# CONNECTIONS.net
KiCad netlist of a schematic drawn in Altium Designer
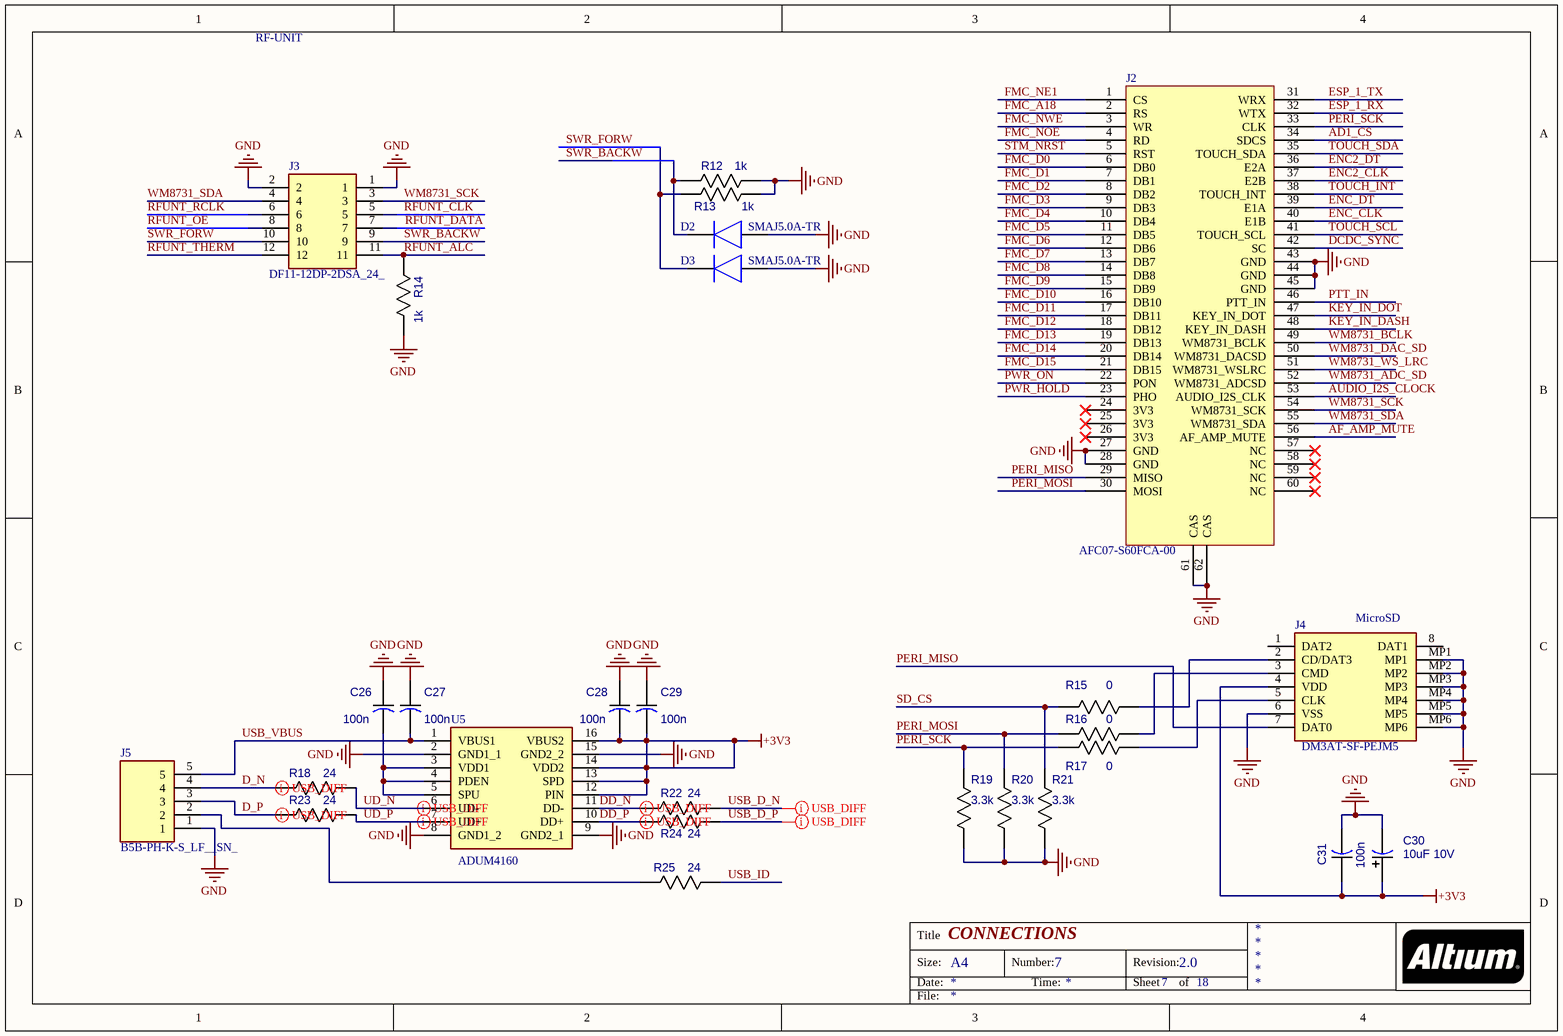
[diagram p0: CONNECTIONS.SchDoc]

(export (version "E")
  (design (tool "Eeschema 10.0.6"))
  (components
    (comp (ref "C26")
      (value "100n")
      (footprint "CAP_0805")
      (description "CAP_0805")
      (libsource (lib "*") (part "CAP_0805"))
    )
    (comp (ref "C27")
      (value "100n")
      (footprint "CAP_0805")
      (description "CAP_0805")
      (libsource (lib "*") (part "CAP_0805"))
    )
    (comp (ref "C28")
      (value "100n")
      (footprint "CAP_0805")
      (description "CAP_0805")
      (libsource (lib "*") (part "CAP_0805"))
    )
    (comp (ref "C29")
      (value "100n")
      (footprint "CAP_0805")
      (description "CAP_0805")
      (libsource (lib "*") (part "CAP_0805"))
    )
    (comp (ref "C30")
      (value "10uF 10V")
      (footprint "CAPAE_4.3x4.3h5.4")
      (description "CAPAE_4.3x4.3h5.4")
      (fields (field (name "Comment") "22uF 10V"))
      (libsource (lib "*") (part "CAPAE_4.3x4.3h5.4"))
    )
    (comp (ref "C31")
      (value "100n")
      (footprint "CAP_0805")
      (description "CAP_0805")
      (libsource (lib "") (part "CAP_0805_1"))
    )
    (comp (ref "D2")
      (value "SMAJ5.0A-TR")
      (footprint "SMBJ36CATR")
      (description "Diode")
      (fields
        (field (name "MANUFACTURER_PART_NUMBER") "SMLVT3V3")
        (field (name "MOUSER PART NUMBER") "511-SMLVT3V3")
      )
      (libsource (lib "*") (part "SMLVT3V3"))
    )
    (comp (ref "D3")
      (value "SMAJ5.0A-TR")
      (footprint "SMBJ36CATR")
      (description "Diode")
      (fields
        (field (name "MANUFACTURER_PART_NUMBER") "SMLVT3V3")
        (field (name "MOUSER PART NUMBER") "511-SMLVT3V3")
      )
      (libsource (lib "*") (part "SMLVT3V3"))
    )
    (comp (ref "J2")
      (value "AFC07-S60FCA-00")
      (footprint "AFC07-S60FCA-00")
      (libsource (lib "MOTHERBOARD") (part "AFC07-S60FCA-00"))
    )
    (comp (ref "J3")
      (value "DF11-12DP-2DSA_24_")
      (footprint "SamacSys:SHDR12W60P200_2X6_1400X500X690P")
      (description "Connector")
      (fields
        (field (name "MANUFACTURER_PART_NUMBER") "DF11-12DP-2DSA(24)")
        (field (name "MOUSER PART NUMBER") "798-DF11-12DP-2DSA24")
      )
      (libsource (lib "*") (part "DF11-12DP-2DSA_24_"))
    )
    (comp (ref "J4")
      (value "DM3AT-SF-PEJM5")
      (footprint "SamacSys:DM3ATSFPEJM5")
      (description "Connector")
      (libsource (lib "*") (part "DM3AT-SF-PEJM5"))
    )
    (comp (ref "J5")
      (value "B5B-PH-K-S_LF__SN_")
      (footprint "SamacSys:SHDR5W50P0X200_1X5_1190X450X600P")
      (description "Connector")
      (fields (field (name "MANUFACTURER_PART_NUMBER") "B5B-PH-K-S(LF)(SN)"))
      (libsource (lib "SamacSys") (part "B5B-PH-K-S_LF__SN_"))
    )
    (comp (ref "R12")
      (value "1k")
      (footprint "RES_0805")
      (description "RES_0805")
      (libsource (lib "") (part "RES_0805_1"))
    )
    (comp (ref "R13")
      (value "1k")
      (footprint "RES_0805")
      (description "RES_0805")
      (libsource (lib "") (part "RES_0805_1"))
    )
    (comp (ref "R14")
      (value "1k")
      (footprint "RES_0805")
      (description "RES_0805")
      (libsource (lib "") (part "RES_0805_1"))
    )
    (comp (ref "R15")
      (value "0")
      (footprint "RES_0805")
      (description "RES_0805")
      (libsource (lib "*") (part "RES_0805"))
    )
    (comp (ref "R16")
      (value "0")
      (footprint "RES_0805")
      (description "RES_0805")
      (libsource (lib "*") (part "RES_0805"))
    )
    (comp (ref "R17")
      (value "0")
      (footprint "RES_0805")
      (description "RES_0805")
      (libsource (lib "*") (part "RES_0805"))
    )
    (comp (ref "R18")
      (value "24")
      (footprint "RES_0805")
      (description "RES_0805")
      (libsource (lib "") (part "RES_0805_1"))
    )
    (comp (ref "R19")
      (value "3.3k")
      (footprint "RES_0805")
      (description "RES_0805")
      (libsource (lib "*") (part "RES_0805"))
    )
    (comp (ref "R20")
      (value "3.3k")
      (footprint "RES_0805")
      (description "RES_0805")
      (libsource (lib "*") (part "RES_0805"))
    )
    (comp (ref "R21")
      (value "3.3k")
      (footprint "RES_0805")
      (description "RES_0805")
      (libsource (lib "*") (part "RES_0805"))
    )
    (comp (ref "R22")
      (value "24")
      (footprint "RES_0805")
      (description "RES_0805")
      (libsource (lib "") (part "RES_0805_1"))
    )
    (comp (ref "R23")
      (value "24")
      (footprint "RES_0805")
      (description "RES_0805")
      (libsource (lib "") (part "RES_0805_1"))
    )
    (comp (ref "R24")
      (value "24")
      (footprint "RES_0805")
      (description "RES_0805")
      (libsource (lib "") (part "RES_0805_1"))
    )
    (comp (ref "R25")
      (value "24")
      (footprint "RES_0805")
      (description "RES_0805")
      (libsource (lib "") (part "RES_0805_1"))
    )
    (comp (ref "U5")
      (value "ADUM4160")
      (footprint "SOIC127P1032X265-16N")
      (description "Integrated Circuit")
      (fields
        (field (name "MANUFACTURER_PART_NUMBER") "ADUM4160BRWZ")
        (field (name "MOUSER PART NUMBER") "584-ADUM4160BRWZ")
      )
      (libsource (lib "*") (part "ADUM4160BRWZ"))
    )
  )
  (nets
    (net (code "1") (name "+3V3") (class "Default")
      (node (ref "C28") (pin "2") (pinfunction "2_2") (pintype "passive"))
      (node (ref "C29") (pin "2") (pinfunction "2_2") (pintype "passive"))
      (node (ref "C30") (pin "1") (pinfunction "PLUS_1") (pintype "passive"))
      (node (ref "C31") (pin "1") (pinfunction "1_1") (pintype "passive"))
      (node (ref "J4") (pin "4") (pinfunction "VDD_4") (pintype "passive"))
      (node (ref "U5") (pin "12") (pinfunction "PIN_12") (pintype "passive"))
      (node (ref "U5") (pin "13") (pinfunction "SPD_13") (pintype "passive"))
      (node (ref "U5") (pin "14") (pinfunction "VDD2_14") (pintype "passive"))
      (node (ref "U5") (pin "16") (pinfunction "VBUS2_16") (pintype "passive"))
    )
    (net (code "2") (name "/AD1_CS") (class "Default")
      (node (ref "J2") (pin "34") (pinfunction "SDCS_34") (pintype "passive"))
    )
    (net (code "3") (name "/AF_AMP_MUTE") (class "Default")
      (node (ref "J2") (pin "56") (pinfunction "AF_AMP_MUTE_56") (pintype "passive"))
    )
    (net (code "4") (name "/AUDIO_I2S_CLOCK") (class "Default")
      (node (ref "J2") (pin "53") (pinfunction "AUDIO_I2S_CLK_53") (pintype "passive"))
    )
    (net (code "5") (name "/DCDC_SYNC") (class "Default")
      (node (ref "J2") (pin "42") (pinfunction "SC_42") (pintype "passive"))
    )
    (net (code "6") (name "/DD_N") (class "Default")
      (node (ref "R22") (pin "1") (pinfunction "1_1") (pintype "passive"))
      (node (ref "U5") (pin "11") (pinfunction "DD-_11") (pintype "passive"))
    )
    (net (code "7") (name "/DD_P") (class "Default")
      (node (ref "R24") (pin "1") (pinfunction "1_1") (pintype "passive"))
      (node (ref "U5") (pin "10") (pinfunction "DD+_10") (pintype "passive"))
    )
    (net (code "8") (name "/D_N") (class "Default")
      (node (ref "J5") (pin "4") (pinfunction "4_4") (pintype "passive"))
      (node (ref "R18") (pin "1") (pinfunction "1_1") (pintype "passive"))
    )
    (net (code "9") (name "/D_P") (class "Default")
      (node (ref "J5") (pin "3") (pinfunction "3_3") (pintype "passive"))
      (node (ref "R23") (pin "1") (pinfunction "1_1") (pintype "passive"))
    )
    (net (code "10") (name "/ENC2_CLK") (class "Default")
      (node (ref "J2") (pin "37") (pinfunction "E2B_37") (pintype "passive"))
    )
    (net (code "11") (name "/ENC2_DT") (class "Default")
      (node (ref "J2") (pin "36") (pinfunction "E2A_36") (pintype "passive"))
    )
    (net (code "12") (name "/ENC_CLK") (class "Default")
      (node (ref "J2") (pin "40") (pinfunction "E1B_40") (pintype "passive"))
    )
    (net (code "13") (name "/ENC_DT") (class "Default")
      (node (ref "J2") (pin "39") (pinfunction "E1A_39") (pintype "passive"))
    )
    (net (code "14") (name "/ESP_1_RX") (class "Default")
      (node (ref "J2") (pin "32") (pinfunction "WTX_32") (pintype "passive"))
    )
    (net (code "15") (name "/ESP_1_TX") (class "Default")
      (node (ref "J2") (pin "31") (pinfunction "WRX_31") (pintype "passive"))
    )
    (net (code "16") (name "/FMC_A18") (class "Default")
      (node (ref "J2") (pin "2") (pinfunction "RS_2") (pintype "passive"))
    )
    (net (code "17") (name "/FMC_D0") (class "Default")
      (node (ref "J2") (pin "6") (pinfunction "DB0_6") (pintype "passive"))
    )
    (net (code "18") (name "/FMC_D1") (class "Default")
      (node (ref "J2") (pin "7") (pinfunction "DB1_7") (pintype "passive"))
    )
    (net (code "19") (name "/FMC_D2") (class "Default")
      (node (ref "J2") (pin "8") (pinfunction "DB2_8") (pintype "passive"))
    )
    (net (code "20") (name "/FMC_D3") (class "Default")
      (node (ref "J2") (pin "9") (pinfunction "DB3_9") (pintype "passive"))
    )
    (net (code "21") (name "/FMC_D4") (class "Default")
      (node (ref "J2") (pin "10") (pinfunction "DB4_10") (pintype "passive"))
    )
    (net (code "22") (name "/FMC_D5") (class "Default")
      (node (ref "J2") (pin "11") (pinfunction "DB5_11") (pintype "passive"))
    )
    (net (code "23") (name "/FMC_D6") (class "Default")
      (node (ref "J2") (pin "12") (pinfunction "DB6_12") (pintype "passive"))
    )
    (net (code "24") (name "/FMC_D7") (class "Default")
      (node (ref "J2") (pin "13") (pinfunction "DB7_13") (pintype "passive"))
    )
    (net (code "25") (name "/FMC_D8") (class "Default")
      (node (ref "J2") (pin "14") (pinfunction "DB8_14") (pintype "passive"))
    )
    (net (code "26") (name "/FMC_D9") (class "Default")
      (node (ref "J2") (pin "15") (pinfunction "DB9_15") (pintype "passive"))
    )
    (net (code "27") (name "/FMC_D10") (class "Default")
      (node (ref "J2") (pin "16") (pinfunction "DB10_16") (pintype "passive"))
    )
    (net (code "28") (name "/FMC_D11") (class "Default")
      (node (ref "J2") (pin "17") (pinfunction "DB11_17") (pintype "passive"))
    )
    (net (code "29") (name "/FMC_D12") (class "Default")
      (node (ref "J2") (pin "18") (pinfunction "DB12_18") (pintype "passive"))
    )
    (net (code "30") (name "/FMC_D13") (class "Default")
      (node (ref "J2") (pin "19") (pinfunction "DB13_19") (pintype "passive"))
    )
    (net (code "31") (name "/FMC_D14") (class "Default")
      (node (ref "J2") (pin "20") (pinfunction "DB14_20") (pintype "passive"))
    )
    (net (code "32") (name "/FMC_D15") (class "Default")
      (node (ref "J2") (pin "21") (pinfunction "DB15_21") (pintype "passive"))
    )
    (net (code "33") (name "/FMC_NE1") (class "Default")
      (node (ref "J2") (pin "1") (pinfunction "CS_1") (pintype "passive"))
    )
    (net (code "34") (name "/FMC_NOE") (class "Default")
      (node (ref "J2") (pin "4") (pinfunction "RD_4") (pintype "passive"))
    )
    (net (code "35") (name "/FMC_NWE") (class "Default")
      (node (ref "J2") (pin "3") (pinfunction "WR_3") (pintype "passive"))
    )
    (net (code "36") (name "/KEY_IN_DASH") (class "Default")
      (node (ref "J2") (pin "48") (pinfunction "KEY_IN_DASH_48") (pintype "passive"))
    )
    (net (code "37") (name "/KEY_IN_DOT") (class "Default")
      (node (ref "J2") (pin "47") (pinfunction "KEY_IN_DOT_47") (pintype "passive"))
    )
    (net (code "38") (name "/PERI_MISO") (class "Default")
      (node (ref "J2") (pin "29") (pinfunction "MISO_29") (pintype "passive"))
      (node (ref "J4") (pin "7") (pinfunction "DAT0_7") (pintype "passive"))
    )
    (net (code "39") (name "/PERI_MOSI") (class "Default")
      (node (ref "J2") (pin "30") (pinfunction "MOSI_30") (pintype "passive"))
      (node (ref "R16") (pin "2") (pinfunction "2_2") (pintype "passive"))
      (node (ref "R20") (pin "2") (pinfunction "2_2") (pintype "passive"))
    )
    (net (code "40") (name "/PERI_SCK") (class "Default")
      (node (ref "J2") (pin "33") (pinfunction "CLK_33") (pintype "passive"))
      (node (ref "R17") (pin "2") (pinfunction "2_2") (pintype "passive"))
      (node (ref "R19") (pin "2") (pinfunction "2_2") (pintype "passive"))
    )
    (net (code "41") (name "/PTT_IN") (class "Default")
      (node (ref "J2") (pin "46") (pinfunction "PTT_IN_46") (pintype "passive"))
    )
    (net (code "42") (name "/PWR_HOLD") (class "Default")
      (node (ref "J2") (pin "23") (pinfunction "PHO_23") (pintype "passive"))
    )
    (net (code "43") (name "/PWR_ON") (class "Default")
      (node (ref "J2") (pin "22") (pinfunction "PON_22") (pintype "passive"))
    )
    (net (code "44") (name "/RFUNT_ALC") (class "Default")
      (node (ref "J3") (pin "11") (pinfunction "11_11") (pintype "passive"))
      (node (ref "R14") (pin "1") (pinfunction "1_1") (pintype "passive"))
    )
    (net (code "45") (name "/RFUNT_CLK") (class "Default")
      (node (ref "J3") (pin "5") (pinfunction "5_5") (pintype "passive"))
    )
    (net (code "46") (name "/RFUNT_DATA") (class "Default")
      (node (ref "J3") (pin "7") (pinfunction "7_7") (pintype "passive"))
    )
    (net (code "47") (name "/RFUNT_OE") (class "Default")
      (node (ref "J3") (pin "8") (pinfunction "8_8") (pintype "passive"))
    )
    (net (code "48") (name "/RFUNT_RCLK") (class "Default")
      (node (ref "J3") (pin "6") (pinfunction "6_6") (pintype "passive"))
    )
    (net (code "49") (name "/RFUNT_THERM") (class "Default")
      (node (ref "J3") (pin "12") (pinfunction "12_12") (pintype "passive"))
    )
    (net (code "50") (name "/SD_CS") (class "Default")
      (node (ref "R15") (pin "2") (pinfunction "2_2") (pintype "passive"))
      (node (ref "R21") (pin "2") (pinfunction "2_2") (pintype "passive"))
    )
    (net (code "51") (name "/STM_NRST") (class "Default")
      (node (ref "J2") (pin "5") (pinfunction "RST_5") (pintype "passive"))
    )
    (net (code "52") (name "/SWR_BACKW") (class "Default")
      (node (ref "D2") (pin "1") (pinfunction "K_1") (pintype "passive"))
      (node (ref "J3") (pin "9") (pinfunction "9_9") (pintype "passive"))
      (node (ref "R12") (pin "1") (pinfunction "1_1") (pintype "passive"))
    )
    (net (code "53") (name "/SWR_FORW") (class "Default")
      (node (ref "D3") (pin "1") (pinfunction "K_1") (pintype "passive"))
      (node (ref "J3") (pin "10") (pinfunction "10_10") (pintype "passive"))
      (node (ref "R13") (pin "1") (pinfunction "1_1") (pintype "passive"))
    )
    (net (code "54") (name "/TOUCH_INT") (class "Default")
      (node (ref "J2") (pin "38") (pinfunction "TOUCH_INT_38") (pintype "passive"))
    )
    (net (code "55") (name "/TOUCH_SCL") (class "Default")
      (node (ref "J2") (pin "41") (pinfunction "TOUCH_SCL_41") (pintype "passive"))
    )
    (net (code "56") (name "/TOUCH_SDA") (class "Default")
      (node (ref "J2") (pin "35") (pinfunction "TOUCH_SDA_35") (pintype "passive"))
    )
    (net (code "57") (name "/UD_N") (class "Default")
      (node (ref "R18") (pin "2") (pinfunction "2_2") (pintype "passive"))
      (node (ref "U5") (pin "6") (pinfunction "UD-_6") (pintype "passive"))
    )
    (net (code "58") (name "/UD_P") (class "Default")
      (node (ref "R23") (pin "2") (pinfunction "2_2") (pintype "passive"))
      (node (ref "U5") (pin "7") (pinfunction "UD+_7") (pintype "passive"))
    )
    (net (code "59") (name "/USB_D_N") (class "Default")
      (node (ref "R22") (pin "2") (pinfunction "2_2") (pintype "passive"))
    )
    (net (code "60") (name "/USB_D_P") (class "Default")
      (node (ref "R24") (pin "2") (pinfunction "2_2") (pintype "passive"))
    )
    (net (code "61") (name "/USB_ID") (class "Default")
      (node (ref "R25") (pin "2") (pinfunction "2_2") (pintype "passive"))
    )
    (net (code "62") (name "/USB_VBUS") (class "Default")
      (node (ref "C27") (pin "2") (pinfunction "2_2") (pintype "passive"))
      (node (ref "J5") (pin "5") (pinfunction "5_5") (pintype "passive"))
      (node (ref "U5") (pin "1") (pinfunction "VBUS1_1") (pintype "passive"))
    )
    (net (code "63") (name "/WM8731_ADC_SD") (class "Default")
      (node (ref "J2") (pin "52") (pinfunction "WM8731_ADCSD_52") (pintype "passive"))
    )
    (net (code "64") (name "/WM8731_BCLK") (class "Default")
      (node (ref "J2") (pin "49") (pinfunction "WM8731_BCLK_49") (pintype "passive"))
    )
    (net (code "65") (name "/WM8731_DAC_SD") (class "Default")
      (node (ref "J2") (pin "50") (pinfunction "WM8731_DACSD_50") (pintype "passive"))
    )
    (net (code "66") (name "/WM8731_SCK") (class "Default")
      (node (ref "J2") (pin "54") (pinfunction "WM8731_SCK_54") (pintype "passive"))
      (node (ref "J3") (pin "3") (pinfunction "3_3") (pintype "passive"))
    )
    (net (code "67") (name "/WM8731_SDA") (class "Default")
      (node (ref "J2") (pin "55") (pinfunction "WM8731_SDA_55") (pintype "passive"))
      (node (ref "J3") (pin "4") (pinfunction "4_4") (pintype "passive"))
    )
    (net (code "68") (name "/WM8731_WS_LRC") (class "Default")
      (node (ref "J2") (pin "51") (pinfunction "WM8731_WSLRC_51") (pintype "passive"))
    )
    (net (code "69") (name "GND") (class "Default")
      (node (ref "C26") (pin "1") (pinfunction "1_1") (pintype "passive"))
      (node (ref "C27") (pin "1") (pinfunction "1_1") (pintype "passive"))
      (node (ref "C28") (pin "1") (pinfunction "1_1") (pintype "passive"))
      (node (ref "C29") (pin "1") (pinfunction "1_1") (pintype "passive"))
      (node (ref "C30") (pin "2") (pinfunction "MINUS_2") (pintype "passive"))
      (node (ref "C31") (pin "2") (pinfunction "2_2") (pintype "passive"))
      (node (ref "D2") (pin "2") (pinfunction "A_2") (pintype "passive"))
      (node (ref "D3") (pin "2") (pinfunction "A_2") (pintype "passive"))
      (node (ref "J2") (pin "27") (pinfunction "GND_27") (pintype "passive"))
      (node (ref "J2") (pin "28") (pinfunction "GND_28") (pintype "passive"))
      (node (ref "J2") (pin "43") (pinfunction "GND_43") (pintype "passive"))
      (node (ref "J2") (pin "44") (pinfunction "GND_44") (pintype "passive"))
      (node (ref "J2") (pin "45") (pinfunction "GND_45") (pintype "passive"))
      (node (ref "J2") (pin "61") (pinfunction "CAS_61") (pintype "passive"))
      (node (ref "J2") (pin "62") (pinfunction "CAS_62") (pintype "passive"))
      (node (ref "J3") (pin "1") (pinfunction "1_1") (pintype "passive"))
      (node (ref "J3") (pin "2") (pinfunction "2_2") (pintype "passive"))
      (node (ref "J4") (pin "6") (pinfunction "VSS_6") (pintype "passive"))
      (node (ref "J4") (pin "MP1") (pinfunction "MP1_MP1") (pintype "passive"))
      (node (ref "J4") (pin "MP2") (pinfunction "MP2_MP2") (pintype "passive"))
      (node (ref "J4") (pin "MP3") (pinfunction "MP3_MP3") (pintype "passive"))
      (node (ref "J4") (pin "MP4") (pinfunction "MP4_MP4") (pintype "passive"))
      (node (ref "J4") (pin "MP5") (pinfunction "MP5_MP5") (pintype "passive"))
      (node (ref "J4") (pin "MP6") (pinfunction "MP6_MP6") (pintype "passive"))
      (node (ref "J5") (pin "1") (pinfunction "1_1") (pintype "passive"))
      (node (ref "R12") (pin "2") (pinfunction "2_2") (pintype "passive"))
      (node (ref "R13") (pin "2") (pinfunction "2_2") (pintype "passive"))
      (node (ref "R14") (pin "2") (pinfunction "2_2") (pintype "passive"))
      (node (ref "R19") (pin "1") (pinfunction "1_1") (pintype "passive"))
      (node (ref "R20") (pin "1") (pinfunction "1_1") (pintype "passive"))
      (node (ref "R21") (pin "1") (pinfunction "1_1") (pintype "passive"))
      (node (ref "U5") (pin "15") (pinfunction "GND2_2_15") (pintype "passive"))
      (node (ref "U5") (pin "2") (pinfunction "GND1_1_2") (pintype "passive"))
      (node (ref "U5") (pin "8") (pinfunction "GND1_2_8") (pintype "passive"))
      (node (ref "U5") (pin "9") (pinfunction "GND2_1_9") (pintype "passive"))
    )
    (net (code "70") (name "Net-(J4-CD{slash}DAT3)") (class "Default")
      (node (ref "J4") (pin "2") (pinfunction "CD/DAT3_2") (pintype "passive"))
      (node (ref "R15") (pin "1") (pinfunction "1_1") (pintype "passive"))
    )
    (net (code "71") (name "Net-(J4-CLK)") (class "Default")
      (node (ref "J4") (pin "5") (pinfunction "CLK_5") (pintype "passive"))
      (node (ref "R17") (pin "1") (pinfunction "1_1") (pintype "passive"))
    )
    (net (code "72") (name "Net-(J4-CMD)") (class "Default")
      (node (ref "J4") (pin "3") (pinfunction "CMD_3") (pintype "passive"))
      (node (ref "R16") (pin "1") (pinfunction "1_1") (pintype "passive"))
    )
    (net (code "73") (name "Net-(J5-Pad2)") (class "Default")
      (node (ref "J5") (pin "2") (pinfunction "2_2") (pintype "passive"))
      (node (ref "R25") (pin "1") (pinfunction "1_1") (pintype "passive"))
    )
    (net (code "74") (name "Net-(U5-PDEN)") (class "Default")
      (node (ref "C26") (pin "2") (pinfunction "2_2") (pintype "passive"))
      (node (ref "U5") (pin "3") (pinfunction "VDD1_3") (pintype "passive"))
      (node (ref "U5") (pin "4") (pinfunction "PDEN_4") (pintype "passive"))
      (node (ref "U5") (pin "5") (pinfunction "SPU_5") (pintype "passive"))
    )
    (net (code "75") (name "unconnected-(J2-3V3-Pad24)") (class "Default")
      (node (ref "J2") (pin "24") (pinfunction "3V3_24") (pintype "passive+no_connect"))
    )
    (net (code "76") (name "unconnected-(J2-3V3-Pad25)") (class "Default")
      (node (ref "J2") (pin "25") (pinfunction "3V3_25") (pintype "passive+no_connect"))
    )
    (net (code "77") (name "unconnected-(J2-3V3-Pad26)") (class "Default")
      (node (ref "J2") (pin "26") (pinfunction "3V3_26") (pintype "passive+no_connect"))
    )
    (net (code "78") (name "unconnected-(J2-NC-Pad57)") (class "Default")
      (node (ref "J2") (pin "57") (pinfunction "NC_57") (pintype "passive+no_connect"))
    )
    (net (code "79") (name "unconnected-(J2-NC-Pad58)") (class "Default")
      (node (ref "J2") (pin "58") (pinfunction "NC_58") (pintype "passive+no_connect"))
    )
    (net (code "80") (name "unconnected-(J2-NC-Pad59)") (class "Default")
      (node (ref "J2") (pin "59") (pinfunction "NC_59") (pintype "passive+no_connect"))
    )
    (net (code "81") (name "unconnected-(J2-NC-Pad60)") (class "Default")
      (node (ref "J2") (pin "60") (pinfunction "NC_60") (pintype "passive+no_connect"))
    )
    (net (code "82") (name "unconnected-(J4-DAT1-Pad8)") (class "Default")
      (node (ref "J4") (pin "8") (pinfunction "DAT1_8") (pintype "passive"))
    )
    (net (code "83") (name "unconnected-(J4-DAT2-Pad1)") (class "Default")
      (node (ref "J4") (pin "1") (pinfunction "DAT2_1") (pintype "passive"))
    )
  )
)
